# Clock.net
KiCad netlist of a schematic drawn in Altium Designer
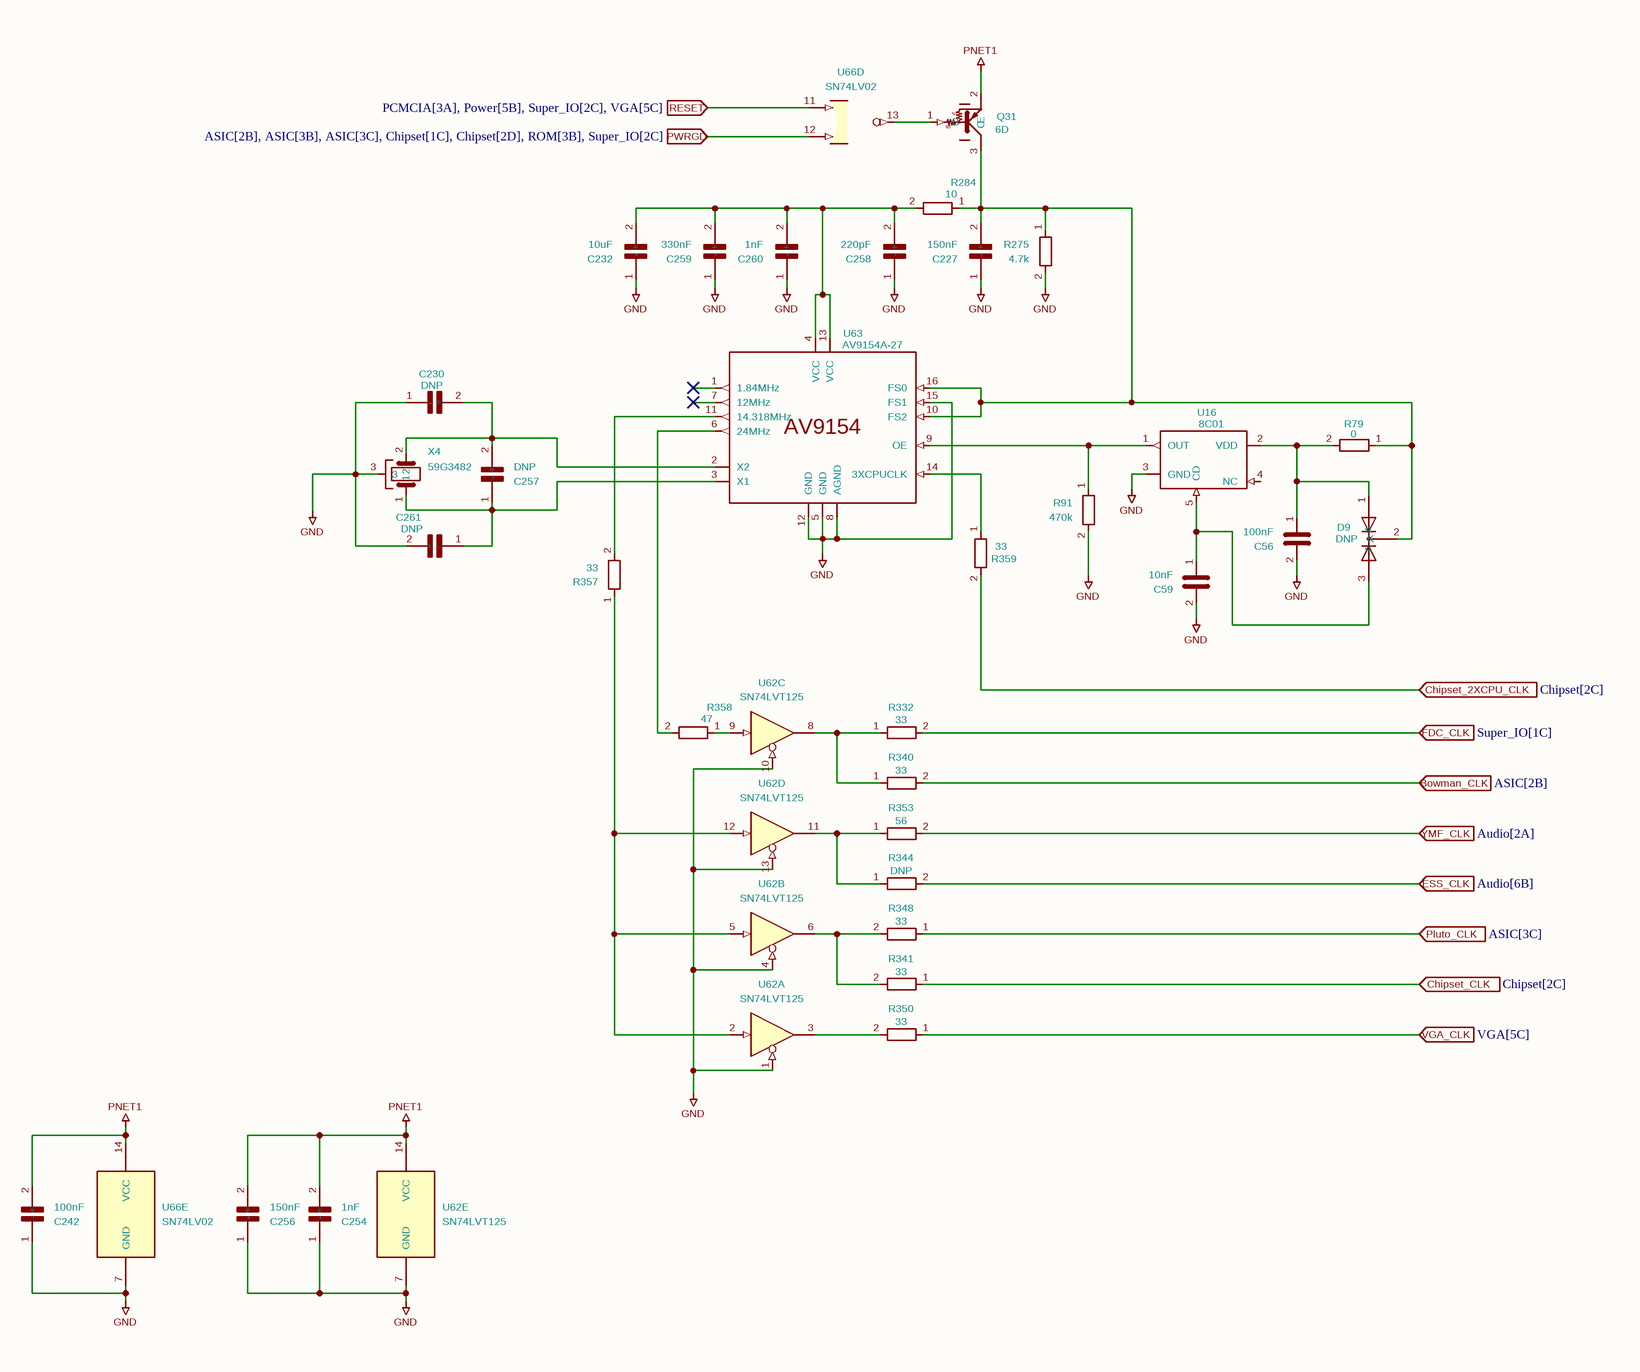
[diagram p0: Clock.SchDoc]

(export (version "E")
  (design (tool "Eeschema 10.0.6"))
  (components
    (comp (ref "C56") (value "100nF") (footprint "C_0402_1005Metric") (libsource (lib "Device") (part "C")))
    (comp (ref "C59") (value "10nF") (footprint "C_0603_1608Metric") (libsource (lib "Device") (part "C")))
    (comp (ref "C227") (value "150nF") (footprint "C_0402_1005Metric") (libsource (lib "") (part "C_1")))
    (comp (ref "C230") (value "DNP") (footprint "C_0402_1005Metric") (libsource (lib "") (part "C_1")))
    (comp (ref "C232") (value "10uF") (footprint "C_1206_3216Metric") (libsource (lib "") (part "C_1")))
    (comp (ref "C242")
      (value "100nF")
      (footprint "C_0402_1005Metric")
      (libsource (lib "PCM_Elektuur") (part "C"))
    )
    (comp (ref "C254")
      (value "1nF")
      (footprint "C_0402_1005Metric")
      (libsource (lib "PCM_Elektuur") (part "C"))
    )
    (comp (ref "C256")
      (value "150nF")
      (footprint "C_0402_1005Metric")
      (libsource (lib "PCM_Elektuur") (part "C"))
    )
    (comp (ref "C257")
      (value "DNP")
      (footprint "C_0402_1005Metric")
      (libsource (lib "PCM_Elektuur") (part "C"))
    )
    (comp (ref "C258") (value "220pF") (footprint "C_0402_1005Metric") (libsource (lib "") (part "C_1")))
    (comp (ref "C259") (value "330nF") (footprint "C_0603_1608Metric") (libsource (lib "") (part "C_1")))
    (comp (ref "C260") (value "1nF") (footprint "C_0402_1005Metric") (libsource (lib "") (part "C_1")))
    (comp (ref "C261") (value "DNP") (footprint "C_0402_1005Metric") (libsource (lib "") (part "C_2")))
    (comp (ref "D9")
      (value "DNP")
      (footprint "3D")
      (libsource (lib "Device") (part "D_Dual_CommonCathode_AKA"))
    )
    (comp (ref "Q31") (value "6D") (footprint "SOT-23") (libsource (lib "Transistor_BJT") (part "DTA114Y")))
    (comp (ref "R79") (value "0") (footprint "R_0402_1005Metric") (libsource (lib "Device") (part "R")))
    (comp (ref "R91") (value "470k") (footprint "R_0402_1005Metric") (libsource (lib "") (part "R_2")))
    (comp (ref "R275") (value "4.7k") (footprint "R_0402_1005Metric") (libsource (lib "") (part "R_2")))
    (comp (ref "R284") (value "10") (footprint "R_0805_2012Metric") (libsource (lib "") (part "R_2")))
    (comp (ref "R332") (value "33") (footprint "R_0402_1005Metric") (libsource (lib "") (part "R_1")))
    (comp (ref "R340") (value "33") (footprint "R_0402_1005Metric") (libsource (lib "") (part "R_1")))
    (comp (ref "R341") (value "33") (footprint "R_0402_1005Metric") (libsource (lib "Device") (part "R")))
    (comp (ref "R344") (value "DNP") (footprint "R_0402_1005Metric") (libsource (lib "") (part "R_1")))
    (comp (ref "R348") (value "33") (footprint "R_0402_1005Metric") (libsource (lib "Device") (part "R")))
    (comp (ref "R350") (value "33") (footprint "R_0402_1005Metric") (libsource (lib "Device") (part "R")))
    (comp (ref "R353") (value "56") (footprint "R_0402_1005Metric") (libsource (lib "") (part "R_1")))
    (comp (ref "R357") (value "33") (footprint "R_0402_1005Metric") (libsource (lib "") (part "R_1")))
    (comp (ref "R358") (value "47") (footprint "R_0402_1005Metric") (libsource (lib "") (part "R_2")))
    (comp (ref "R359") (value "33") (footprint "R_0402_1005Metric") (libsource (lib "") (part "R_2")))
    (comp (ref "U16") (value "8C01") (footprint "SOT-23-5") (libsource (lib "PC110") (part "QC01")))
    (comp (ref "U62")
      (value "SN74LVT125")
      (footprint "TSSOP-14_4.4x5mm_P0.65mm")
      (libsource (lib "74xx") (part "74LS125"))
    )
    (comp (ref "U63") (value "AV9154A-27") (footprint "SOIC-16W") (libsource (lib "PC110") (part "AV9154")))
    (comp (ref "U66")
      (value "SN74LV02")
      (footprint "TSSOP-14_4.4x5mm_P0.65mm")
      (libsource (lib "74xx") (part "74LS02"))
    )
    (comp (ref "X4") (value "59G3482") (footprint "XTAL-6") (libsource (lib "Device") (part "Crystal_GND3")))
  )
  (nets
    (net (code "1") (name "/Bowman_CLK") (class "Default")
      (node (ref "R340") (pin "2") (pinfunction "2_2") (pintype "passive"))
    )
    (net (code "2") (name "/Chipset_2XCPU_CLK") (class "Default")
      (node (ref "R359") (pin "2") (pinfunction "2_2") (pintype "passive"))
    )
    (net (code "3") (name "/Chipset_CLK") (class "Default")
      (node (ref "R341") (pin "1") (pinfunction "1_1") (pintype "passive"))
    )
    (net (code "4") (name "/ESS_CLK") (class "Default")
      (node (ref "R344") (pin "2") (pinfunction "2_2") (pintype "passive"))
    )
    (net (code "5") (name "/FDC_CLK") (class "Default")
      (node (ref "R332") (pin "2") (pinfunction "2_2") (pintype "passive"))
    )
    (net (code "6") (name "/PWRGD") (class "Default")
      (node (ref "U66") (pin "12") (pinfunction "12_12") (pintype "input"))
    )
    (net (code "7") (name "/Pluto_CLK") (class "Default")
      (node (ref "R348") (pin "1") (pinfunction "1_1") (pintype "passive"))
    )
    (net (code "8") (name "/RESET") (class "Default")
      (node (ref "U66") (pin "11") (pinfunction "11_11") (pintype "input"))
    )
    (net (code "9") (name "/VGA_CLK") (class "Default")
      (node (ref "R350") (pin "1") (pinfunction "1_1") (pintype "passive"))
    )
    (net (code "10") (name "/YMF_CLK") (class "Default")
      (node (ref "R353") (pin "2") (pinfunction "2_2") (pintype "passive"))
    )
    (net (code "11") (name "GND") (class "Default")
      (node (ref "C227") (pin "1") (pinfunction "+_1") (pintype "passive"))
      (node (ref "C230") (pin "1") (pinfunction "+_1") (pintype "passive"))
      (node (ref "C232") (pin "1") (pinfunction "+_1") (pintype "passive"))
      (node (ref "C242") (pin "1") (pinfunction "+_1") (pintype "passive"))
      (node (ref "C254") (pin "1") (pinfunction "+_1") (pintype "passive"))
      (node (ref "C256") (pin "1") (pinfunction "+_1") (pintype "passive"))
      (node (ref "C258") (pin "1") (pinfunction "+_1") (pintype "passive"))
      (node (ref "C259") (pin "1") (pinfunction "+_1") (pintype "passive"))
      (node (ref "C260") (pin "1") (pinfunction "+_1") (pintype "passive"))
      (node (ref "C261") (pin "2") (pinfunction "-_2") (pintype "passive"))
      (node (ref "C56") (pin "2") (pinfunction "2_2") (pintype "passive"))
      (node (ref "C59") (pin "2") (pinfunction "2_2") (pintype "passive"))
      (node (ref "R275") (pin "2") (pinfunction "2_2") (pintype "passive"))
      (node (ref "R91") (pin "2") (pinfunction "2_2") (pintype "passive"))
      (node (ref "U16") (pin "3") (pinfunction "GND_3") (pintype "power_in"))
      (node (ref "U62") (pin "1") (pinfunction "1_1") (pintype "input"))
      (node (ref "U62") (pin "10") (pinfunction "10_10") (pintype "input"))
      (node (ref "U62") (pin "13") (pinfunction "13_13") (pintype "input"))
      (node (ref "U62") (pin "4") (pinfunction "4_4") (pintype "input"))
      (node (ref "U62") (pin "7") (pinfunction "GND_7") (pintype "power_in"))
      (node (ref "U63") (pin "12") (pinfunction "GND_12") (pintype "power_in"))
      (node (ref "U63") (pin "15") (pinfunction "FS1_15") (pintype "input"))
      (node (ref "U63") (pin "5") (pinfunction "GND_5") (pintype "power_in"))
      (node (ref "U63") (pin "8") (pinfunction "AGND_8") (pintype "power_in"))
      (node (ref "U66") (pin "7") (pinfunction "GND_7") (pintype "power_in"))
      (node (ref "X4") (pin "3") (pinfunction "3_3") (pintype "passive"))
    )
    (net (code "12") (name "Net-(C227--)") (class "Default")
      (node (ref "C227") (pin "2") (pinfunction "-_2") (pintype "passive"))
      (node (ref "D9") (pin "2") (pinfunction "K_2") (pintype "passive"))
      (node (ref "Q31") (pin "3") (pinfunction "C_3") (pintype "passive"))
      (node (ref "R275") (pin "1") (pinfunction "1_1") (pintype "passive"))
      (node (ref "R284") (pin "1") (pinfunction "1_1") (pintype "passive"))
      (node (ref "R79") (pin "1") (pinfunction "1_1") (pintype "passive"))
      (node (ref "U63") (pin "10") (pinfunction "FS2_10") (pintype "input"))
      (node (ref "U63") (pin "16") (pinfunction "FS0_16") (pintype "input"))
    )
    (net (code "13") (name "Net-(C230--)") (class "Default")
      (node (ref "C230") (pin "2") (pinfunction "-_2") (pintype "passive"))
      (node (ref "C257") (pin "2") (pinfunction "-_2") (pintype "passive"))
      (node (ref "U63") (pin "2") (pinfunction "X2_2") (pintype "bidirectional"))
      (node (ref "X4") (pin "2") (pinfunction "2_2") (pintype "passive"))
    )
    (net (code "14") (name "Net-(C232--)") (class "Default")
      (node (ref "C232") (pin "2") (pinfunction "-_2") (pintype "passive"))
      (node (ref "C258") (pin "2") (pinfunction "-_2") (pintype "passive"))
      (node (ref "C259") (pin "2") (pinfunction "-_2") (pintype "passive"))
      (node (ref "C260") (pin "2") (pinfunction "-_2") (pintype "passive"))
      (node (ref "R284") (pin "2") (pinfunction "2_2") (pintype "passive"))
      (node (ref "U63") (pin "13") (pinfunction "VCC_13") (pintype "power_in"))
      (node (ref "U63") (pin "4") (pinfunction "VCC_4") (pintype "power_in"))
    )
    (net (code "15") (name "Net-(C257-+)") (class "Default")
      (node (ref "C257") (pin "1") (pinfunction "+_1") (pintype "passive"))
      (node (ref "C261") (pin "1") (pinfunction "+_1") (pintype "passive"))
      (node (ref "U63") (pin "3") (pinfunction "X1_3") (pintype "bidirectional"))
      (node (ref "X4") (pin "1") (pinfunction "1_1") (pintype "passive"))
    )
    (net (code "16") (name "Net-(Q31-B)") (class "Default")
      (node (ref "Q31") (pin "1") (pinfunction "B_1") (pintype "input"))
      (node (ref "U66") (pin "13") (pinfunction "13_13") (pintype "output"))
    )
    (net (code "17") (name "Net-(R332-Pad1)") (class "Default")
      (node (ref "R332") (pin "1") (pinfunction "1_1") (pintype "passive"))
      (node (ref "R340") (pin "1") (pinfunction "1_1") (pintype "passive"))
      (node (ref "U62") (pin "8") (pinfunction "8_8") (pintype "tri_state"))
    )
    (net (code "18") (name "Net-(R341-Pad2)") (class "Default")
      (node (ref "R341") (pin "2") (pinfunction "2_2") (pintype "passive"))
      (node (ref "R348") (pin "2") (pinfunction "2_2") (pintype "passive"))
      (node (ref "U62") (pin "6") (pinfunction "6_6") (pintype "tri_state"))
    )
    (net (code "19") (name "Net-(R344-Pad1)") (class "Default")
      (node (ref "R344") (pin "1") (pinfunction "1_1") (pintype "passive"))
      (node (ref "R353") (pin "1") (pinfunction "1_1") (pintype "passive"))
      (node (ref "U62") (pin "11") (pinfunction "11_11") (pintype "tri_state"))
    )
    (net (code "20") (name "Net-(R350-Pad2)") (class "Default")
      (node (ref "R350") (pin "2") (pinfunction "2_2") (pintype "passive"))
      (node (ref "U62") (pin "3") (pinfunction "3_3") (pintype "tri_state"))
    )
    (net (code "21") (name "Net-(R357-Pad1)") (class "Default")
      (node (ref "R357") (pin "1") (pinfunction "1_1") (pintype "passive"))
      (node (ref "U62") (pin "12") (pinfunction "12_12") (pintype "input"))
      (node (ref "U62") (pin "2") (pinfunction "2_2") (pintype "input"))
      (node (ref "U62") (pin "5") (pinfunction "5_5") (pintype "input"))
    )
    (net (code "22") (name "Net-(R358-Pad1)") (class "Default")
      (node (ref "R358") (pin "1") (pinfunction "1_1") (pintype "passive"))
      (node (ref "U62") (pin "9") (pinfunction "9_9") (pintype "input"))
    )
    (net (code "23") (name "Net-(U16-CD)") (class "Default")
      (node (ref "C59") (pin "1") (pinfunction "1_1") (pintype "passive"))
      (node (ref "D9") (pin "3") (pinfunction "A_3") (pintype "passive"))
      (node (ref "U16") (pin "5") (pinfunction "CD_5") (pintype "input"))
    )
    (net (code "24") (name "Net-(U16-OUT)") (class "Default")
      (node (ref "R91") (pin "1") (pinfunction "1_1") (pintype "passive"))
      (node (ref "U16") (pin "1") (pinfunction "OUT_1") (pintype "output"))
      (node (ref "U63") (pin "9") (pinfunction "OE_9") (pintype "input"))
    )
    (net (code "25") (name "Net-(U16-VDD)") (class "Default")
      (node (ref "C56") (pin "1") (pinfunction "1_1") (pintype "passive"))
      (node (ref "D9") (pin "1") (pinfunction "A_1") (pintype "passive"))
      (node (ref "R79") (pin "2") (pinfunction "2_2") (pintype "passive"))
      (node (ref "U16") (pin "2") (pinfunction "VDD_2") (pintype "power_in"))
    )
    (net (code "26") (name "Net-(U63-3XCPUCLK)") (class "Default")
      (node (ref "R359") (pin "1") (pinfunction "1_1") (pintype "passive"))
      (node (ref "U63") (pin "14") (pinfunction "3XCPUCLK_14") (pintype "input"))
    )
    (net (code "27") (name "Net-(U63-14.318MHz)") (class "Default")
      (node (ref "R357") (pin "2") (pinfunction "2_2") (pintype "passive"))
      (node (ref "U63") (pin "11") (pinfunction "14.318MHz_11") (pintype "output"))
    )
    (net (code "28") (name "Net-(U63-24MHz)") (class "Default")
      (node (ref "R358") (pin "2") (pinfunction "2_2") (pintype "passive"))
      (node (ref "U63") (pin "6") (pinfunction "24MHz_6") (pintype "output"))
    )
    (net (code "29") (name "PNET1") (class "Default")
      (node (ref "C242") (pin "2") (pinfunction "-_2") (pintype "passive"))
      (node (ref "C254") (pin "2") (pinfunction "-_2") (pintype "passive"))
      (node (ref "C256") (pin "2") (pinfunction "-_2") (pintype "passive"))
      (node (ref "Q31") (pin "2") (pinfunction "E_2") (pintype "passive"))
      (node (ref "U62") (pin "14") (pinfunction "VCC_14") (pintype "power_in"))
      (node (ref "U66") (pin "14") (pinfunction "VCC_14") (pintype "power_in"))
    )
    (net (code "30") (name "unconnected-(U16-NC-Pad4)") (class "Default")
      (node (ref "U16") (pin "4") (pinfunction "NC_4") (pintype "input"))
    )
    (net (code "31") (name "unconnected-(U63-1.84MHz-Pad1)") (class "Default")
      (node (ref "U63") (pin "1") (pinfunction "1.84MHz_1") (pintype "output+no_connect"))
    )
    (net (code "32") (name "unconnected-(U63-12MHz-Pad7)") (class "Default")
      (node (ref "U63") (pin "7") (pinfunction "12MHz_7") (pintype "output+no_connect"))
    )
  )
)
